# AVR_ISP_Adaptor.net
KiCad netlist of a schematic drawn in Altium Designer
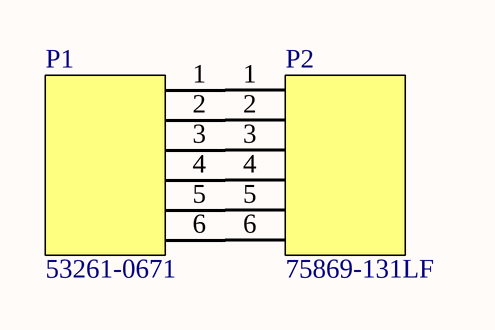
[diagram p0: AVR_ISP_Adaptor.SchDoc]

(export (version "E")
  (design (tool "Eeschema 10.0.6"))
  (components
    (comp (ref "P1")
      (value "53261-0671")
      (footprint "53261-0671")
      (description "CONN HEADER 6POS 1.25MM R/A SMD")
      (fields (field (name "MANUFACTURER") "Molex Inc"))
      (libsource (lib "My Schematic Library") (part "53261-0671"))
    )
    (comp (ref "P2")
      (value "75869-131LF")
      (footprint "75869-131LF")
      (description "CONN HEADER 6POS DUAL VERT PCB")
      (fields (field (name "MANUFACTURER") "FCI"))
      (libsource (lib "My Schematic Library") (part "75869-131LF"))
    )
  )
  (nets
    (net (code "1") (name "Net-(P1-Pad1)") (class "Default")
      (node (ref "P1") (pin "1") (pintype "passive"))
      (node (ref "P2") (pin "1") (pintype "passive"))
    )
    (net (code "2") (name "Net-(P1-Pad2)") (class "Default")
      (node (ref "P1") (pin "2") (pintype "passive"))
      (node (ref "P2") (pin "2") (pintype "passive"))
    )
    (net (code "3") (name "Net-(P1-Pad3)") (class "Default")
      (node (ref "P1") (pin "3") (pintype "passive"))
      (node (ref "P2") (pin "3") (pintype "passive"))
    )
    (net (code "4") (name "Net-(P1-Pad4)") (class "Default")
      (node (ref "P1") (pin "4") (pintype "passive"))
      (node (ref "P2") (pin "4") (pintype "passive"))
    )
    (net (code "5") (name "Net-(P1-Pad5)") (class "Default")
      (node (ref "P1") (pin "5") (pintype "passive"))
      (node (ref "P2") (pin "5") (pintype "passive"))
    )
    (net (code "6") (name "Net-(P1-Pad6)") (class "Default")
      (node (ref "P1") (pin "6") (pintype "passive"))
      (node (ref "P2") (pin "6") (pintype "passive"))
    )
  )
)
